# finger-1.net
KiCad netlist of a schematic drawn in EAGLE
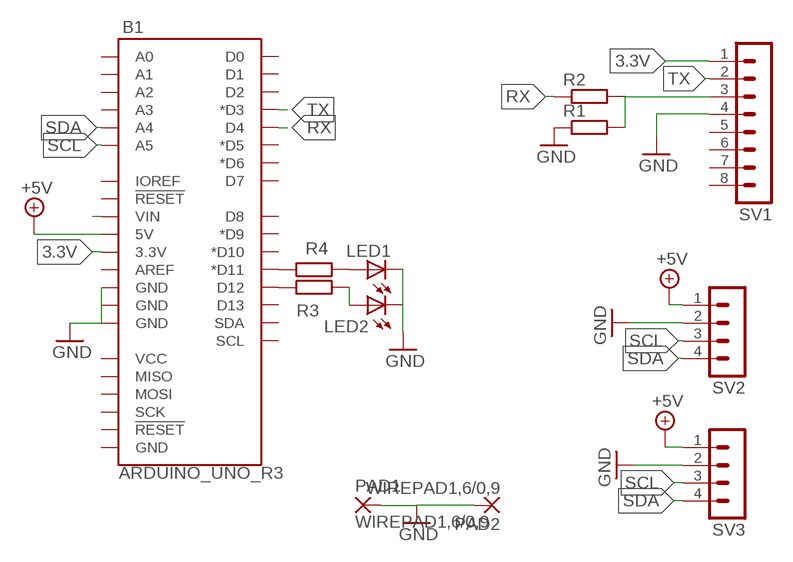
[diagram p0: schematic, sheet 1]

(export (version "E")
  (design (tool "Eeschema 10.0.6"))
  (components
    (comp (ref "B1")
      (value "ARDUINO_UNO_R3")
      (footprint "eagle-import:ARDUINO_R3")
      (libsource (lib "eagle-import") (part "ARDUINO_UNO_R3"))
    )
    (comp (ref "LED1")
      (value "LED3MM")
      (footprint "eagle-import:LED3MM")
      (libsource (lib "eagle-import") (part "LED3MM"))
    )
    (comp (ref "LED2")
      (value "LED3MM")
      (footprint "eagle-import:LED3MM")
      (libsource (lib "eagle-import") (part "LED3MM"))
    )
    (comp (ref "PAD1")
      (value "WIREPAD1,6/0,9")
      (footprint "eagle-import:1,6_0,9")
      (libsource (lib "eagle-import") (part "WIREPAD1,6/0,9"))
    )
    (comp (ref "PAD2")
      (value "WIREPAD1,6/0,9")
      (footprint "eagle-import:1,6_0,9")
      (libsource (lib "eagle-import") (part "WIREPAD1,6/0,9"))
    )
    (comp (ref "R1")
      (value "R-EU_0207/7")
      (footprint "eagle-import:0207_7")
      (libsource (lib "eagle-import") (part "R-EU_0207/7"))
    )
    (comp (ref "R2")
      (value "R-EU_0207/7")
      (footprint "eagle-import:0207_7")
      (libsource (lib "eagle-import") (part "R-EU_0207/7"))
    )
    (comp (ref "R3")
      (value "R-EU_0207/7")
      (footprint "eagle-import:0207_7")
      (libsource (lib "eagle-import") (part "R-EU_0207/7"))
    )
    (comp (ref "R4")
      (value "R-EU_0207/7")
      (footprint "eagle-import:0207_7")
      (libsource (lib "eagle-import") (part "R-EU_0207/7"))
    )
    (comp (ref "SV1")
      (value "MA08-1")
      (footprint "eagle-import:MA08-1")
      (libsource (lib "eagle-import") (part "MA08-1"))
    )
    (comp (ref "SV2")
      (value "MA04-1")
      (footprint "eagle-import:MA04-1")
      (libsource (lib "eagle-import") (part "MA04-1"))
    )
    (comp (ref "SV3")
      (value "MA04-1")
      (footprint "eagle-import:MA04-1")
      (libsource (lib "eagle-import") (part "MA04-1"))
    )
  )
  (nets
    (net (code "1") (name "+5V") (class "Default")
      (node (ref "B1") (pin "5V") (pinfunction "5V_5V") (pintype "bidirectional"))
      (node (ref "SV2") (pin "1") (pinfunction "1_1") (pintype "passive"))
      (node (ref "SV3") (pin "1") (pinfunction "1_1") (pintype "passive"))
    )
    (net (code "2") (name "3.3V") (class "Default")
      (node (ref "B1") (pin "3.3V") (pinfunction "3.3V_3.3V") (pintype "bidirectional"))
      (node (ref "SV1") (pin "1") (pinfunction "1_1") (pintype "passive"))
    )
    (net (code "3") (name "GND") (class "Default")
      (node (ref "B1") (pin "GND@2") (pinfunction "GND_GND@2") (pintype "bidirectional"))
      (node (ref "B1") (pin "GND@3") (pinfunction "GND_GND@3") (pintype "bidirectional"))
      (node (ref "B1") (pin "GND@4") (pinfunction "GND_GND@4") (pintype "bidirectional"))
      (node (ref "LED1") (pin "K") (pinfunction "C_K") (pintype "passive"))
      (node (ref "LED2") (pin "K") (pinfunction "C_K") (pintype "passive"))
      (node (ref "PAD1") (pin "1") (pinfunction "P_1") (pintype "passive"))
      (node (ref "PAD2") (pin "1") (pinfunction "P_1") (pintype "passive"))
      (node (ref "R1") (pin "1") (pinfunction "1_1") (pintype "passive"))
      (node (ref "SV1") (pin "4") (pinfunction "4_4") (pintype "passive"))
      (node (ref "SV2") (pin "2") (pinfunction "2_2") (pintype "passive"))
      (node (ref "SV3") (pin "2") (pinfunction "2_2") (pintype "passive"))
    )
    (net (code "4") (name "Net-(B1-*D11)") (class "Default")
      (node (ref "B1") (pin "D11") (pinfunction "*D11_D11") (pintype "bidirectional"))
      (node (ref "R4") (pin "1") (pinfunction "1_1") (pintype "passive"))
    )
    (net (code "5") (name "Net-(B1-PadD12)") (class "Default")
      (node (ref "B1") (pin "D12") (pinfunction "D12_D12") (pintype "bidirectional"))
      (node (ref "R3") (pin "1") (pinfunction "1_1") (pintype "passive"))
    )
    (net (code "6") (name "Net-(LED1-PadA)") (class "Default")
      (node (ref "LED1") (pin "A") (pinfunction "A_A") (pintype "passive"))
      (node (ref "R4") (pin "2") (pinfunction "2_2") (pintype "passive"))
    )
    (net (code "7") (name "Net-(LED2-PadA)") (class "Default")
      (node (ref "LED2") (pin "A") (pinfunction "A_A") (pintype "passive"))
      (node (ref "R3") (pin "2") (pinfunction "2_2") (pintype "passive"))
    )
    (net (code "8") (name "Net-(R1-Pad2)") (class "Default")
      (node (ref "R1") (pin "2") (pinfunction "2_2") (pintype "passive"))
      (node (ref "R2") (pin "2") (pinfunction "2_2") (pintype "passive"))
      (node (ref "SV1") (pin "3") (pinfunction "3_3") (pintype "passive"))
    )
    (net (code "9") (name "RX") (class "Default")
      (node (ref "B1") (pin "D4") (pinfunction "D4_D4") (pintype "bidirectional"))
      (node (ref "R2") (pin "1") (pinfunction "1_1") (pintype "passive"))
    )
    (net (code "10") (name "SCL") (class "Default")
      (node (ref "B1") (pin "A5") (pinfunction "A5_A5") (pintype "bidirectional"))
      (node (ref "SV2") (pin "3") (pinfunction "3_3") (pintype "passive"))
      (node (ref "SV3") (pin "3") (pinfunction "3_3") (pintype "passive"))
    )
    (net (code "11") (name "SDA") (class "Default")
      (node (ref "B1") (pin "A4") (pinfunction "A4_A4") (pintype "bidirectional"))
      (node (ref "SV2") (pin "4") (pinfunction "4_4") (pintype "passive"))
      (node (ref "SV3") (pin "4") (pinfunction "4_4") (pintype "passive"))
    )
    (net (code "12") (name "TX") (class "Default")
      (node (ref "B1") (pin "D3") (pinfunction "*D3_D3") (pintype "bidirectional"))
      (node (ref "SV1") (pin "2") (pinfunction "2_2") (pintype "passive"))
    )
    (net (code "13") (name "unconnected-(B1-*D5-PadD5)") (class "Default")
      (node (ref "B1") (pin "D5") (pinfunction "*D5_D5") (pintype "bidirectional"))
    )
    (net (code "14") (name "unconnected-(B1-*D6-PadD6)") (class "Default")
      (node (ref "B1") (pin "D6") (pinfunction "*D6_D6") (pintype "bidirectional"))
    )
    (net (code "15") (name "unconnected-(B1-*D9-PadD9)") (class "Default")
      (node (ref "B1") (pin "D9") (pinfunction "*D9_D9") (pintype "bidirectional"))
    )
    (net (code "16") (name "unconnected-(B1-*D10-PadD10)") (class "Default")
      (node (ref "B1") (pin "D10") (pinfunction "*D10_D10") (pintype "bidirectional"))
    )
    (net (code "17") (name "unconnected-(B1-GND-PadGND@1)") (class "Default")
      (node (ref "B1") (pin "GND@1") (pinfunction "GND_GND@1") (pintype "bidirectional"))
    )
    (net (code "18") (name "unconnected-(B1-PadA0)") (class "Default")
      (node (ref "B1") (pin "A0") (pinfunction "A0_A0") (pintype "bidirectional"))
    )
    (net (code "19") (name "unconnected-(B1-PadA1)") (class "Default")
      (node (ref "B1") (pin "A1") (pinfunction "A1_A1") (pintype "bidirectional"))
    )
    (net (code "20") (name "unconnected-(B1-PadA2)") (class "Default")
      (node (ref "B1") (pin "A2") (pinfunction "A2_A2") (pintype "bidirectional"))
    )
    (net (code "21") (name "unconnected-(B1-PadA3)") (class "Default")
      (node (ref "B1") (pin "A3") (pinfunction "A3_A3") (pintype "bidirectional"))
    )
    (net (code "22") (name "unconnected-(B1-PadAREF)") (class "Default")
      (node (ref "B1") (pin "AREF") (pinfunction "AREF_AREF") (pintype "bidirectional"))
    )
    (net (code "23") (name "unconnected-(B1-PadD0)") (class "Default")
      (node (ref "B1") (pin "D0") (pinfunction "D0_D0") (pintype "bidirectional"))
    )
    (net (code "24") (name "unconnected-(B1-PadD1)") (class "Default")
      (node (ref "B1") (pin "D1") (pinfunction "D1_D1") (pintype "bidirectional"))
    )
    (net (code "25") (name "unconnected-(B1-PadD2)") (class "Default")
      (node (ref "B1") (pin "D2") (pinfunction "D2_D2") (pintype "bidirectional"))
    )
    (net (code "26") (name "unconnected-(B1-PadD7)") (class "Default")
      (node (ref "B1") (pin "D7") (pinfunction "D7_D7") (pintype "bidirectional"))
    )
    (net (code "27") (name "unconnected-(B1-PadD8)") (class "Default")
      (node (ref "B1") (pin "D8") (pinfunction "D8_D8") (pintype "bidirectional"))
    )
    (net (code "28") (name "unconnected-(B1-PadD13)") (class "Default")
      (node (ref "B1") (pin "D13") (pinfunction "D13_D13") (pintype "bidirectional"))
    )
    (net (code "29") (name "unconnected-(B1-PadIOREF)") (class "Default")
      (node (ref "B1") (pin "IOREF") (pinfunction "IOREF_IOREF") (pintype "bidirectional"))
    )
    (net (code "30") (name "unconnected-(B1-PadMISO)") (class "Default")
      (node (ref "B1") (pin "MISO") (pinfunction "MISO_MISO") (pintype "bidirectional"))
    )
    (net (code "31") (name "unconnected-(B1-PadMOSI)") (class "Default")
      (node (ref "B1") (pin "MOSI") (pinfunction "MOSI_MOSI") (pintype "bidirectional"))
    )
    (net (code "32") (name "unconnected-(B1-PadSCK)") (class "Default")
      (node (ref "B1") (pin "SCK") (pinfunction "SCK_SCK") (pintype "bidirectional"))
    )
    (net (code "33") (name "unconnected-(B1-PadSCL)") (class "Default")
      (node (ref "B1") (pin "SCL") (pinfunction "SCL_SCL") (pintype "bidirectional"))
    )
    (net (code "34") (name "unconnected-(B1-PadSDA)") (class "Default")
      (node (ref "B1") (pin "SDA") (pinfunction "SDA_SDA") (pintype "bidirectional"))
    )
    (net (code "35") (name "unconnected-(B1-PadVCC)") (class "Default")
      (node (ref "B1") (pin "VCC") (pinfunction "VCC_VCC") (pintype "bidirectional"))
    )
    (net (code "36") (name "unconnected-(B1-PadVIN)") (class "Default")
      (node (ref "B1") (pin "VIN") (pinfunction "VIN_VIN") (pintype "bidirectional"))
    )
    (net (code "37") (name "unconnected-(B1-~{RESET}-PadRESET@1)") (class "Default")
      (node (ref "B1") (pin "RESET@1") (pinfunction "~{RESET}_RESET@1") (pintype "bidirectional"))
    )
    (net (code "38") (name "unconnected-(B1-~{RESET}-PadRESET@2)") (class "Default")
      (node (ref "B1") (pin "RESET@2") (pinfunction "~{RESET}_RESET@2") (pintype "bidirectional"))
    )
    (net (code "39") (name "unconnected-(SV1-Pad5)") (class "Default")
      (node (ref "SV1") (pin "5") (pinfunction "5_5") (pintype "passive"))
    )
    (net (code "40") (name "unconnected-(SV1-Pad6)") (class "Default")
      (node (ref "SV1") (pin "6") (pinfunction "6_6") (pintype "passive"))
    )
    (net (code "41") (name "unconnected-(SV1-Pad7)") (class "Default")
      (node (ref "SV1") (pin "7") (pinfunction "7_7") (pintype "passive"))
    )
    (net (code "42") (name "unconnected-(SV1-Pad8)") (class "Default")
      (node (ref "SV1") (pin "8") (pinfunction "8_8") (pintype "passive"))
    )
  )
)
